# focus_coil_drive.net
KiCad netlist of a schematic drawn in EAGLE
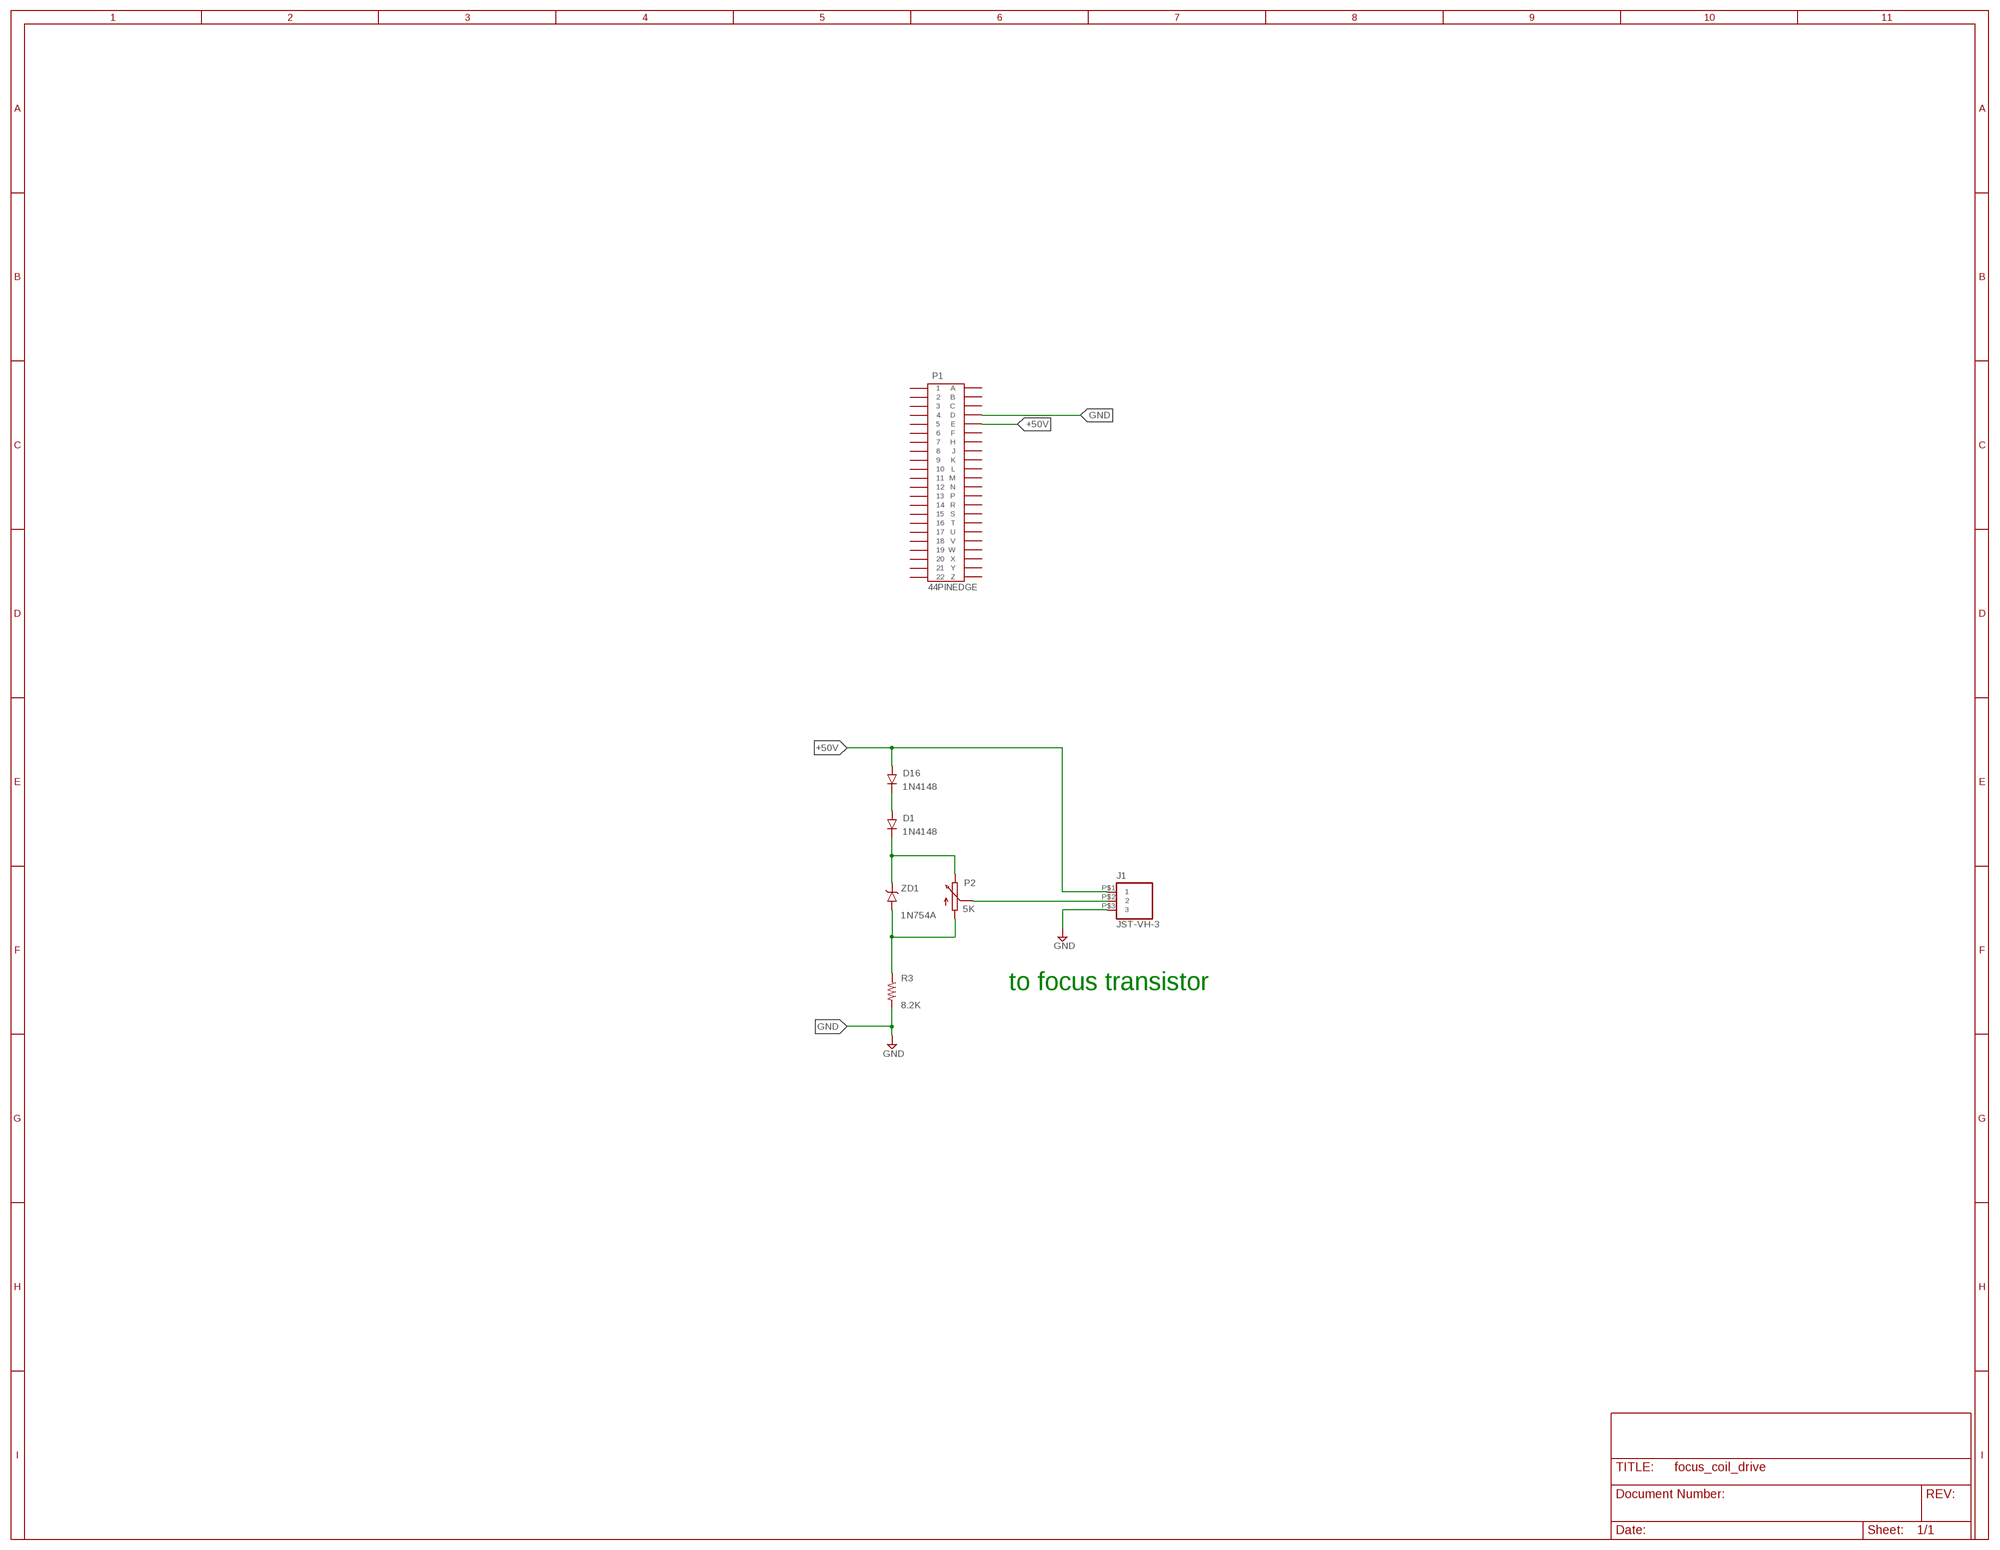
[diagram p0: schematic, sheet 1]

(export (version "E")
  (design (tool "Eeschema 10.0.6"))
  (components
    (comp (ref "D1")
      (value "1N4148")
      (footprint "eagle-import:DO35-7")
      (libsource (lib "eagle-import") (part "1N4148"))
    )
    (comp (ref "D16")
      (value "1N4148")
      (footprint "eagle-import:DO35-7")
      (libsource (lib "eagle-import") (part "1N4148"))
    )
    (comp (ref "J1")
      (value "JST-VH-3")
      (footprint "eagle-import:VHR-3N")
      (libsource (lib "eagle-import") (part "JST-VH-3"))
    )
    (comp (ref "P1")
      (value "44PINEDGE")
      (footprint "eagle-import:44PINEDGE")
      (libsource (lib "eagle-import") (part "44PINEDGE"))
    )
    (comp (ref "P2")
      (value "5K")
      (footprint "eagle-import:3006P")
      (libsource (lib "eagle-import") (part "POT-3006P"))
    )
    (comp (ref "R3")
      (value "8.2K")
      (footprint "eagle-import:0207_10")
      (libsource (lib "eagle-import") (part "RES-V"))
    )
    (comp (ref "ZD1")
      (value "1N754A")
      (footprint "eagle-import:DO35-7")
      (libsource (lib "eagle-import") (part "1N754A"))
    )
  )
  (nets
    (net (code "1") (name "+50V") (class "Default")
      (node (ref "D16") (pin "A") (pinfunction "A_A") (pintype "passive"))
      (node (ref "J1") (pin "P$1") (pinfunction "1_P$1") (pintype "bidirectional"))
      (node (ref "P1") (pin "E") (pinfunction "E_E") (pintype "passive"))
    )
    (net (code "2") (name "GND") (class "Default")
      (node (ref "J1") (pin "P$3") (pinfunction "3_P$3") (pintype "bidirectional"))
      (node (ref "P1") (pin "D") (pinfunction "D_D") (pintype "passive"))
      (node (ref "R3") (pin "2") (pinfunction "P$2_2") (pintype "passive"))
    )
    (net (code "3") (name "Net-(D1-PadA)") (class "Default")
      (node (ref "D1") (pin "A") (pinfunction "A_A") (pintype "passive"))
      (node (ref "D16") (pin "C") (pinfunction "C_C") (pintype "passive"))
    )
    (net (code "4") (name "Net-(J1-2)") (class "Default")
      (node (ref "J1") (pin "P$2") (pinfunction "2_P$2") (pintype "bidirectional"))
      (node (ref "P2") (pin "2") (pinfunction "S_2") (pintype "passive"))
    )
    (net (code "5") (name "Net-(P2-A)") (class "Default")
      (node (ref "P2") (pin "1") (pinfunction "A_1") (pintype "passive"))
      (node (ref "R3") (pin "1") (pinfunction "P$1_1") (pintype "passive"))
      (node (ref "ZD1") (pin "A") (pinfunction "A_A") (pintype "passive"))
    )
    (net (code "6") (name "Net-(P2-E)") (class "Default")
      (node (ref "D1") (pin "C") (pinfunction "C_C") (pintype "passive"))
      (node (ref "P2") (pin "3") (pinfunction "E_3") (pintype "passive"))
      (node (ref "ZD1") (pin "C") (pinfunction "C_C") (pintype "passive"))
    )
    (net (code "7") (name "unconnected-(P1-Pad1)") (class "Default")
      (node (ref "P1") (pin "1") (pinfunction "1_1") (pintype "passive"))
    )
    (net (code "8") (name "unconnected-(P1-Pad2)") (class "Default")
      (node (ref "P1") (pin "2") (pinfunction "2_2") (pintype "passive"))
    )
    (net (code "9") (name "unconnected-(P1-Pad3)") (class "Default")
      (node (ref "P1") (pin "3") (pinfunction "3_3") (pintype "passive"))
    )
    (net (code "10") (name "unconnected-(P1-Pad4)") (class "Default")
      (node (ref "P1") (pin "4") (pinfunction "4_4") (pintype "passive"))
    )
    (net (code "11") (name "unconnected-(P1-Pad5)") (class "Default")
      (node (ref "P1") (pin "5") (pinfunction "5_5") (pintype "passive"))
    )
    (net (code "12") (name "unconnected-(P1-Pad6)") (class "Default")
      (node (ref "P1") (pin "6") (pinfunction "6_6") (pintype "passive"))
    )
    (net (code "13") (name "unconnected-(P1-Pad7)") (class "Default")
      (node (ref "P1") (pin "7") (pinfunction "7_7") (pintype "passive"))
    )
    (net (code "14") (name "unconnected-(P1-Pad8)") (class "Default")
      (node (ref "P1") (pin "8") (pinfunction "8_8") (pintype "passive"))
    )
    (net (code "15") (name "unconnected-(P1-Pad9)") (class "Default")
      (node (ref "P1") (pin "9") (pinfunction "9_9") (pintype "passive"))
    )
    (net (code "16") (name "unconnected-(P1-Pad10)") (class "Default")
      (node (ref "P1") (pin "10") (pinfunction "10_10") (pintype "passive"))
    )
    (net (code "17") (name "unconnected-(P1-Pad11)") (class "Default")
      (node (ref "P1") (pin "11") (pinfunction "11_11") (pintype "passive"))
    )
    (net (code "18") (name "unconnected-(P1-Pad12)") (class "Default")
      (node (ref "P1") (pin "12") (pinfunction "12_12") (pintype "passive"))
    )
    (net (code "19") (name "unconnected-(P1-Pad13)") (class "Default")
      (node (ref "P1") (pin "13") (pinfunction "13_13") (pintype "passive"))
    )
    (net (code "20") (name "unconnected-(P1-Pad14)") (class "Default")
      (node (ref "P1") (pin "14") (pinfunction "14_14") (pintype "passive"))
    )
    (net (code "21") (name "unconnected-(P1-Pad15)") (class "Default")
      (node (ref "P1") (pin "15") (pinfunction "15_15") (pintype "passive"))
    )
    (net (code "22") (name "unconnected-(P1-Pad16)") (class "Default")
      (node (ref "P1") (pin "16") (pinfunction "16_16") (pintype "passive"))
    )
    (net (code "23") (name "unconnected-(P1-Pad17)") (class "Default")
      (node (ref "P1") (pin "17") (pinfunction "17_17") (pintype "passive"))
    )
    (net (code "24") (name "unconnected-(P1-Pad18)") (class "Default")
      (node (ref "P1") (pin "18") (pinfunction "18_18") (pintype "passive"))
    )
    (net (code "25") (name "unconnected-(P1-Pad19)") (class "Default")
      (node (ref "P1") (pin "19") (pinfunction "19_19") (pintype "passive"))
    )
    (net (code "26") (name "unconnected-(P1-Pad20)") (class "Default")
      (node (ref "P1") (pin "20") (pinfunction "20_20") (pintype "passive"))
    )
    (net (code "27") (name "unconnected-(P1-Pad21)") (class "Default")
      (node (ref "P1") (pin "21") (pinfunction "21_21") (pintype "passive"))
    )
    (net (code "28") (name "unconnected-(P1-Pad22)") (class "Default")
      (node (ref "P1") (pin "22") (pinfunction "22_22") (pintype "passive"))
    )
    (net (code "29") (name "unconnected-(P1-PadA)") (class "Default")
      (node (ref "P1") (pin "A") (pinfunction "A_A") (pintype "passive"))
    )
    (net (code "30") (name "unconnected-(P1-PadB)") (class "Default")
      (node (ref "P1") (pin "B") (pinfunction "B_B") (pintype "passive"))
    )
    (net (code "31") (name "unconnected-(P1-PadC)") (class "Default")
      (node (ref "P1") (pin "C") (pinfunction "C_C") (pintype "passive"))
    )
    (net (code "32") (name "unconnected-(P1-PadF)") (class "Default")
      (node (ref "P1") (pin "F") (pinfunction "F_F") (pintype "passive"))
    )
    (net (code "33") (name "unconnected-(P1-PadH)") (class "Default")
      (node (ref "P1") (pin "H") (pinfunction "H_H") (pintype "passive"))
    )
    (net (code "34") (name "unconnected-(P1-PadJ)") (class "Default")
      (node (ref "P1") (pin "J") (pinfunction "J_J") (pintype "passive"))
    )
    (net (code "35") (name "unconnected-(P1-PadK)") (class "Default")
      (node (ref "P1") (pin "K") (pinfunction "K_K") (pintype "passive"))
    )
    (net (code "36") (name "unconnected-(P1-PadL)") (class "Default")
      (node (ref "P1") (pin "L") (pinfunction "L_L") (pintype "passive"))
    )
    (net (code "37") (name "unconnected-(P1-PadM)") (class "Default")
      (node (ref "P1") (pin "M") (pinfunction "M_M") (pintype "passive"))
    )
    (net (code "38") (name "unconnected-(P1-PadN)") (class "Default")
      (node (ref "P1") (pin "N") (pinfunction "N_N") (pintype "passive"))
    )
    (net (code "39") (name "unconnected-(P1-PadP)") (class "Default")
      (node (ref "P1") (pin "P") (pinfunction "P_P") (pintype "passive"))
    )
    (net (code "40") (name "unconnected-(P1-PadR)") (class "Default")
      (node (ref "P1") (pin "R") (pinfunction "R_R") (pintype "passive"))
    )
    (net (code "41") (name "unconnected-(P1-PadS)") (class "Default")
      (node (ref "P1") (pin "S") (pinfunction "S_S") (pintype "passive"))
    )
    (net (code "42") (name "unconnected-(P1-PadT)") (class "Default")
      (node (ref "P1") (pin "T") (pinfunction "T_T") (pintype "passive"))
    )
    (net (code "43") (name "unconnected-(P1-PadU)") (class "Default")
      (node (ref "P1") (pin "U") (pinfunction "U_U") (pintype "passive"))
    )
    (net (code "44") (name "unconnected-(P1-PadV)") (class "Default")
      (node (ref "P1") (pin "V") (pinfunction "V_V") (pintype "passive"))
    )
    (net (code "45") (name "unconnected-(P1-PadW)") (class "Default")
      (node (ref "P1") (pin "W") (pinfunction "W_W") (pintype "passive"))
    )
    (net (code "46") (name "unconnected-(P1-PadX)") (class "Default")
      (node (ref "P1") (pin "X") (pinfunction "X_X") (pintype "passive"))
    )
    (net (code "47") (name "unconnected-(P1-PadY)") (class "Default")
      (node (ref "P1") (pin "Y") (pinfunction "Y_Y") (pintype "passive"))
    )
    (net (code "48") (name "unconnected-(P1-PadZ)") (class "Default")
      (node (ref "P1") (pin "Z") (pinfunction "Z_Z") (pintype "passive"))
    )
  )
)
